# mega_connector_shield.net
KiCad netlist of a schematic drawn in EAGLE
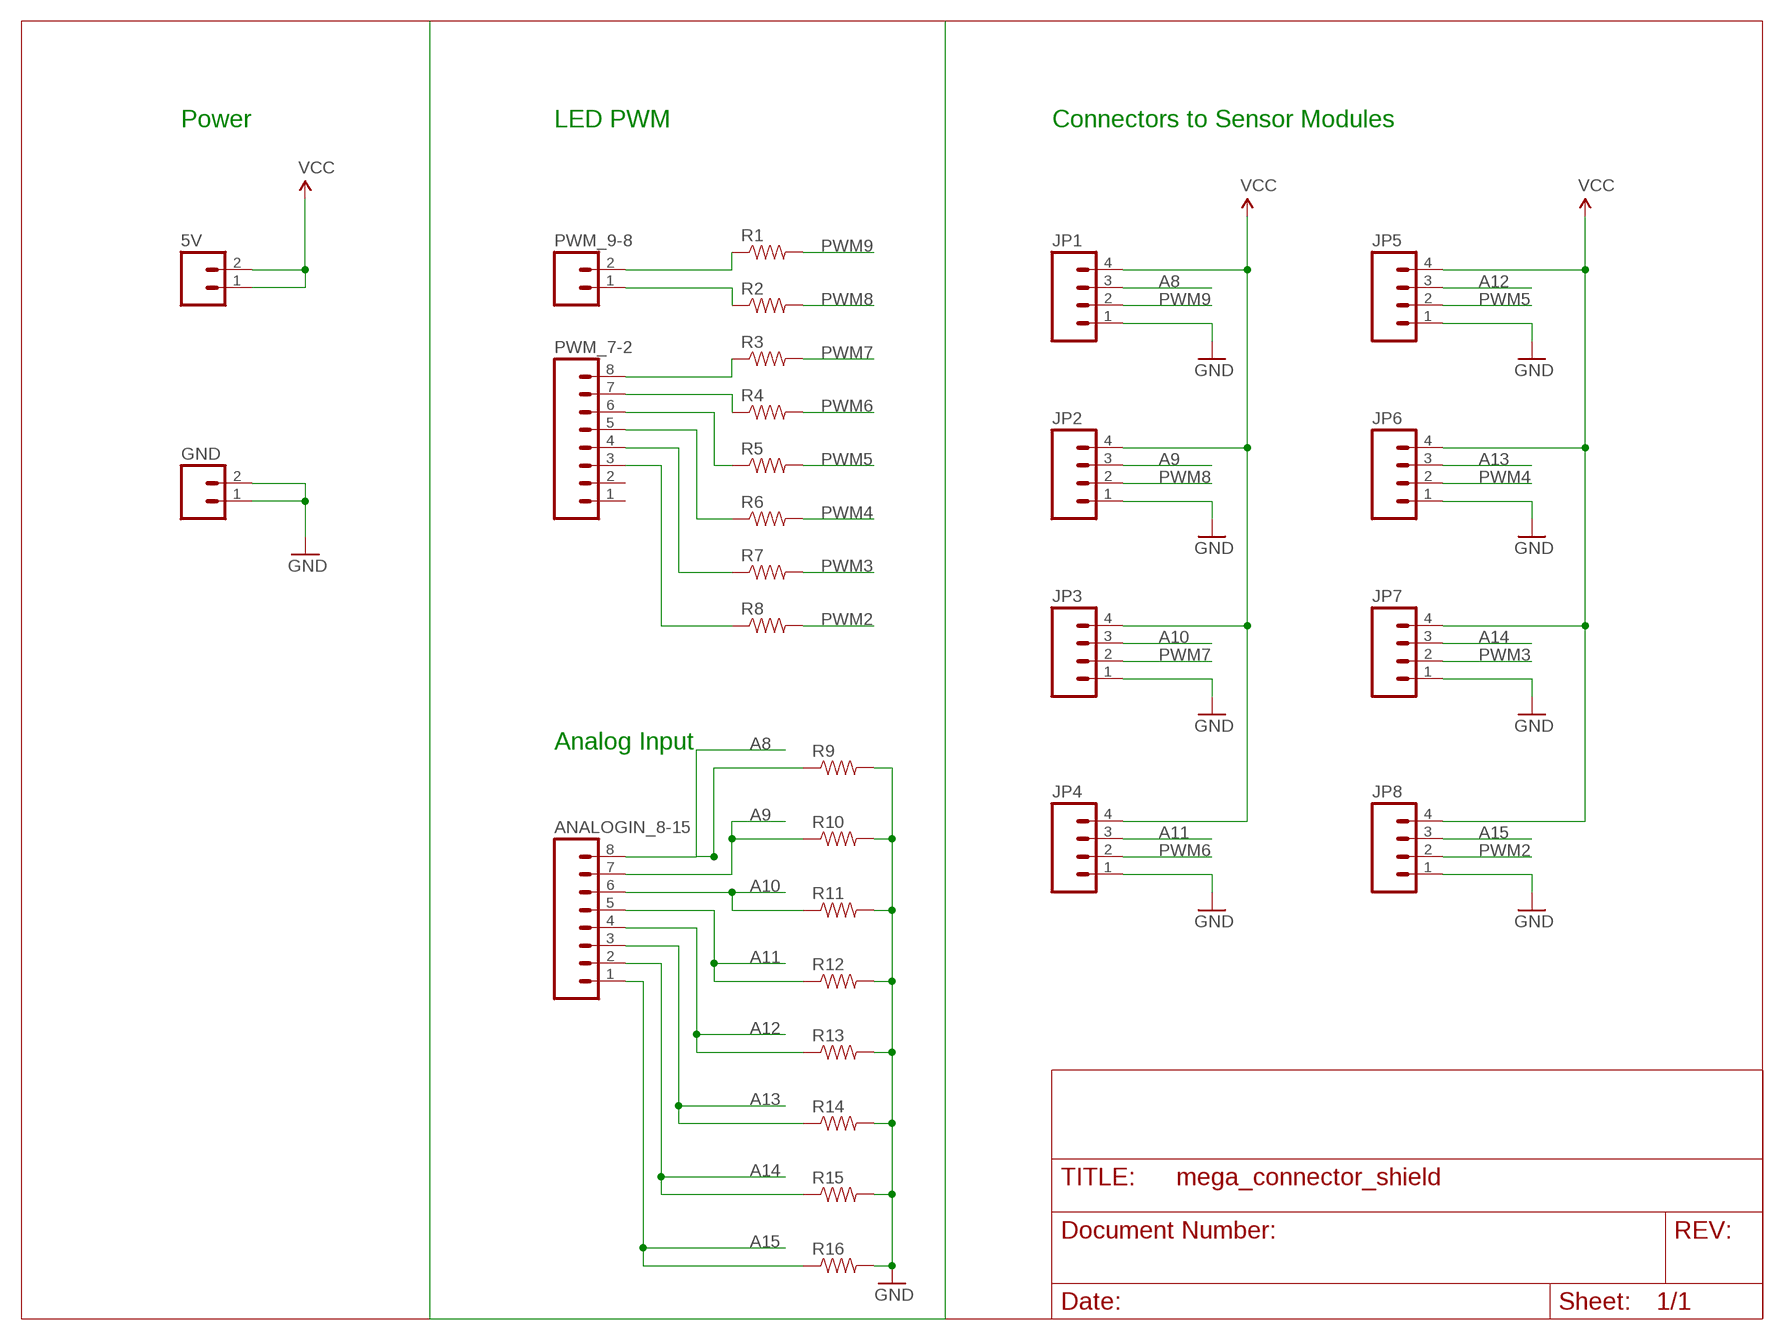
[diagram p0: schematic, sheet 1]

(export (version "E")
  (design (tool "Eeschema 10.0.6"))
  (components
    (comp (ref "5V")
      (value "M02PTH")
      (footprint "eagle-import:1X02")
      (libsource (lib "eagle-import") (part "M02PTH"))
    )
    (comp (ref "ANALOGIN_8-15")
      (value "M08")
      (footprint "eagle-import:1X08_ROUND")
      (libsource (lib "eagle-import") (part "M08"))
    )
    (comp (ref "GND")
      (value "M02PTH")
      (footprint "eagle-import:1X02")
      (libsource (lib "eagle-import") (part "M02PTH"))
    )
    (comp (ref "JP1")
      (value "M04POLAR")
      (footprint "eagle-import:MOLEX-1X4")
      (libsource (lib "eagle-import") (part "M04POLAR"))
    )
    (comp (ref "JP2")
      (value "M04POLAR")
      (footprint "eagle-import:MOLEX-1X4")
      (libsource (lib "eagle-import") (part "M04POLAR"))
    )
    (comp (ref "JP3")
      (value "M04POLAR")
      (footprint "eagle-import:MOLEX-1X4")
      (libsource (lib "eagle-import") (part "M04POLAR"))
    )
    (comp (ref "JP4")
      (value "M04POLAR")
      (footprint "eagle-import:MOLEX-1X4")
      (libsource (lib "eagle-import") (part "M04POLAR"))
    )
    (comp (ref "JP5")
      (value "M04POLAR")
      (footprint "eagle-import:MOLEX-1X4")
      (libsource (lib "eagle-import") (part "M04POLAR"))
    )
    (comp (ref "JP6")
      (value "M04POLAR")
      (footprint "eagle-import:MOLEX-1X4")
      (libsource (lib "eagle-import") (part "M04POLAR"))
    )
    (comp (ref "JP7")
      (value "M04POLAR")
      (footprint "eagle-import:MOLEX-1X4")
      (libsource (lib "eagle-import") (part "M04POLAR"))
    )
    (comp (ref "JP8")
      (value "M04POLAR")
      (footprint "eagle-import:MOLEX-1X4")
      (libsource (lib "eagle-import") (part "M04POLAR"))
    )
    (comp (ref "PWM_7-2")
      (value "M08")
      (footprint "eagle-import:1X08_ROUND")
      (libsource (lib "eagle-import") (part "M08"))
    )
    (comp (ref "PWM_9-8")
      (value "M02PTH")
      (footprint "eagle-import:1X02")
      (libsource (lib "eagle-import") (part "M02PTH"))
    )
    (comp (ref "R1")
      (value "RESISTOR1206")
      (footprint "eagle-import:1206")
      (libsource (lib "eagle-import") (part "RESISTOR1206"))
    )
    (comp (ref "R2")
      (value "RESISTOR1206")
      (footprint "eagle-import:1206")
      (libsource (lib "eagle-import") (part "RESISTOR1206"))
    )
    (comp (ref "R3")
      (value "RESISTOR1206")
      (footprint "eagle-import:1206")
      (libsource (lib "eagle-import") (part "RESISTOR1206"))
    )
    (comp (ref "R4")
      (value "RESISTOR1206")
      (footprint "eagle-import:1206")
      (libsource (lib "eagle-import") (part "RESISTOR1206"))
    )
    (comp (ref "R5")
      (value "RESISTOR1206")
      (footprint "eagle-import:1206")
      (libsource (lib "eagle-import") (part "RESISTOR1206"))
    )
    (comp (ref "R6")
      (value "RESISTOR1206")
      (footprint "eagle-import:1206")
      (libsource (lib "eagle-import") (part "RESISTOR1206"))
    )
    (comp (ref "R7")
      (value "RESISTOR1206")
      (footprint "eagle-import:1206")
      (libsource (lib "eagle-import") (part "RESISTOR1206"))
    )
    (comp (ref "R8")
      (value "RESISTOR1206")
      (footprint "eagle-import:1206")
      (libsource (lib "eagle-import") (part "RESISTOR1206"))
    )
    (comp (ref "R9")
      (value "RESISTOR1206")
      (footprint "eagle-import:1206")
      (libsource (lib "eagle-import") (part "RESISTOR1206"))
    )
    (comp (ref "R10")
      (value "RESISTOR1206")
      (footprint "eagle-import:1206")
      (libsource (lib "eagle-import") (part "RESISTOR1206"))
    )
    (comp (ref "R11")
      (value "RESISTOR1206")
      (footprint "eagle-import:1206")
      (libsource (lib "eagle-import") (part "RESISTOR1206"))
    )
    (comp (ref "R12")
      (value "RESISTOR1206")
      (footprint "eagle-import:1206")
      (libsource (lib "eagle-import") (part "RESISTOR1206"))
    )
    (comp (ref "R13")
      (value "RESISTOR1206")
      (footprint "eagle-import:1206")
      (libsource (lib "eagle-import") (part "RESISTOR1206"))
    )
    (comp (ref "R14")
      (value "RESISTOR1206")
      (footprint "eagle-import:1206")
      (libsource (lib "eagle-import") (part "RESISTOR1206"))
    )
    (comp (ref "R15")
      (value "RESISTOR1206")
      (footprint "eagle-import:1206")
      (libsource (lib "eagle-import") (part "RESISTOR1206"))
    )
    (comp (ref "R16")
      (value "RESISTOR1206")
      (footprint "eagle-import:1206")
      (libsource (lib "eagle-import") (part "RESISTOR1206"))
    )
  )
  (nets
    (net (code "1") (name "/A8") (class "Default")
      (node (ref "ANALOGIN_8-15") (pin "8") (pinfunction "8_8") (pintype "passive"))
      (node (ref "JP1") (pin "3") (pinfunction "3_3") (pintype "passive"))
      (node (ref "R9") (pin "1") (pinfunction "1_1") (pintype "passive"))
    )
    (net (code "2") (name "/A9") (class "Default")
      (node (ref "ANALOGIN_8-15") (pin "7") (pinfunction "7_7") (pintype "passive"))
      (node (ref "JP2") (pin "3") (pinfunction "3_3") (pintype "passive"))
      (node (ref "R10") (pin "1") (pinfunction "1_1") (pintype "passive"))
    )
    (net (code "3") (name "/A10") (class "Default")
      (node (ref "ANALOGIN_8-15") (pin "6") (pinfunction "6_6") (pintype "passive"))
      (node (ref "JP3") (pin "3") (pinfunction "3_3") (pintype "passive"))
      (node (ref "R11") (pin "1") (pinfunction "1_1") (pintype "passive"))
    )
    (net (code "4") (name "/A11") (class "Default")
      (node (ref "ANALOGIN_8-15") (pin "5") (pinfunction "5_5") (pintype "passive"))
      (node (ref "JP4") (pin "3") (pinfunction "3_3") (pintype "passive"))
      (node (ref "R12") (pin "1") (pinfunction "1_1") (pintype "passive"))
    )
    (net (code "5") (name "/A12") (class "Default")
      (node (ref "ANALOGIN_8-15") (pin "4") (pinfunction "4_4") (pintype "passive"))
      (node (ref "JP5") (pin "3") (pinfunction "3_3") (pintype "passive"))
      (node (ref "R13") (pin "1") (pinfunction "1_1") (pintype "passive"))
    )
    (net (code "6") (name "/A13") (class "Default")
      (node (ref "ANALOGIN_8-15") (pin "3") (pinfunction "3_3") (pintype "passive"))
      (node (ref "JP6") (pin "3") (pinfunction "3_3") (pintype "passive"))
      (node (ref "R14") (pin "1") (pinfunction "1_1") (pintype "passive"))
    )
    (net (code "7") (name "/A14") (class "Default")
      (node (ref "ANALOGIN_8-15") (pin "2") (pinfunction "2_2") (pintype "passive"))
      (node (ref "JP7") (pin "3") (pinfunction "3_3") (pintype "passive"))
      (node (ref "R15") (pin "1") (pinfunction "1_1") (pintype "passive"))
    )
    (net (code "8") (name "/A15") (class "Default")
      (node (ref "ANALOGIN_8-15") (pin "1") (pinfunction "1_1") (pintype "passive"))
      (node (ref "JP8") (pin "3") (pinfunction "3_3") (pintype "passive"))
      (node (ref "R16") (pin "1") (pinfunction "1_1") (pintype "passive"))
    )
    (net (code "9") (name "/PWM2") (class "Default")
      (node (ref "JP8") (pin "2") (pinfunction "2_2") (pintype "passive"))
      (node (ref "R8") (pin "2") (pinfunction "2_2") (pintype "passive"))
    )
    (net (code "10") (name "/PWM3") (class "Default")
      (node (ref "JP7") (pin "2") (pinfunction "2_2") (pintype "passive"))
      (node (ref "R7") (pin "2") (pinfunction "2_2") (pintype "passive"))
    )
    (net (code "11") (name "/PWM4") (class "Default")
      (node (ref "JP6") (pin "2") (pinfunction "2_2") (pintype "passive"))
      (node (ref "R6") (pin "2") (pinfunction "2_2") (pintype "passive"))
    )
    (net (code "12") (name "/PWM5") (class "Default")
      (node (ref "JP5") (pin "2") (pinfunction "2_2") (pintype "passive"))
      (node (ref "R5") (pin "2") (pinfunction "2_2") (pintype "passive"))
    )
    (net (code "13") (name "/PWM6") (class "Default")
      (node (ref "JP4") (pin "2") (pinfunction "2_2") (pintype "passive"))
      (node (ref "R4") (pin "2") (pinfunction "2_2") (pintype "passive"))
    )
    (net (code "14") (name "/PWM7") (class "Default")
      (node (ref "JP3") (pin "2") (pinfunction "2_2") (pintype "passive"))
      (node (ref "R3") (pin "2") (pinfunction "2_2") (pintype "passive"))
    )
    (net (code "15") (name "/PWM8") (class "Default")
      (node (ref "JP2") (pin "2") (pinfunction "2_2") (pintype "passive"))
      (node (ref "R2") (pin "2") (pinfunction "2_2") (pintype "passive"))
    )
    (net (code "16") (name "/PWM9") (class "Default")
      (node (ref "JP1") (pin "2") (pinfunction "2_2") (pintype "passive"))
      (node (ref "R1") (pin "2") (pinfunction "2_2") (pintype "passive"))
    )
    (net (code "17") (name "GND") (class "Default")
      (node (ref "GND") (pin "1") (pinfunction "1_1") (pintype "passive"))
      (node (ref "GND") (pin "2") (pinfunction "2_2") (pintype "passive"))
      (node (ref "JP1") (pin "1") (pinfunction "1_1") (pintype "passive"))
      (node (ref "JP2") (pin "1") (pinfunction "1_1") (pintype "passive"))
      (node (ref "JP3") (pin "1") (pinfunction "1_1") (pintype "passive"))
      (node (ref "JP4") (pin "1") (pinfunction "1_1") (pintype "passive"))
      (node (ref "JP5") (pin "1") (pinfunction "1_1") (pintype "passive"))
      (node (ref "JP6") (pin "1") (pinfunction "1_1") (pintype "passive"))
      (node (ref "JP7") (pin "1") (pinfunction "1_1") (pintype "passive"))
      (node (ref "JP8") (pin "1") (pinfunction "1_1") (pintype "passive"))
      (node (ref "R10") (pin "2") (pinfunction "2_2") (pintype "passive"))
      (node (ref "R11") (pin "2") (pinfunction "2_2") (pintype "passive"))
      (node (ref "R12") (pin "2") (pinfunction "2_2") (pintype "passive"))
      (node (ref "R13") (pin "2") (pinfunction "2_2") (pintype "passive"))
      (node (ref "R14") (pin "2") (pinfunction "2_2") (pintype "passive"))
      (node (ref "R15") (pin "2") (pinfunction "2_2") (pintype "passive"))
      (node (ref "R16") (pin "2") (pinfunction "2_2") (pintype "passive"))
      (node (ref "R9") (pin "2") (pinfunction "2_2") (pintype "passive"))
    )
    (net (code "18") (name "Net-(PWM_7-2-Pad3)") (class "Default")
      (node (ref "PWM_7-2") (pin "3") (pinfunction "3_3") (pintype "passive"))
      (node (ref "R8") (pin "1") (pinfunction "1_1") (pintype "passive"))
    )
    (net (code "19") (name "Net-(PWM_7-2-Pad4)") (class "Default")
      (node (ref "PWM_7-2") (pin "4") (pinfunction "4_4") (pintype "passive"))
      (node (ref "R7") (pin "1") (pinfunction "1_1") (pintype "passive"))
    )
    (net (code "20") (name "Net-(PWM_7-2-Pad5)") (class "Default")
      (node (ref "PWM_7-2") (pin "5") (pinfunction "5_5") (pintype "passive"))
      (node (ref "R6") (pin "1") (pinfunction "1_1") (pintype "passive"))
    )
    (net (code "21") (name "Net-(PWM_7-2-Pad6)") (class "Default")
      (node (ref "PWM_7-2") (pin "6") (pinfunction "6_6") (pintype "passive"))
      (node (ref "R5") (pin "1") (pinfunction "1_1") (pintype "passive"))
    )
    (net (code "22") (name "Net-(PWM_7-2-Pad7)") (class "Default")
      (node (ref "PWM_7-2") (pin "7") (pinfunction "7_7") (pintype "passive"))
      (node (ref "R4") (pin "1") (pinfunction "1_1") (pintype "passive"))
    )
    (net (code "23") (name "Net-(PWM_7-2-Pad8)") (class "Default")
      (node (ref "PWM_7-2") (pin "8") (pinfunction "8_8") (pintype "passive"))
      (node (ref "R3") (pin "1") (pinfunction "1_1") (pintype "passive"))
    )
    (net (code "24") (name "Net-(PWM_9-8-Pad1)") (class "Default")
      (node (ref "PWM_9-8") (pin "1") (pinfunction "1_1") (pintype "passive"))
      (node (ref "R2") (pin "1") (pinfunction "1_1") (pintype "passive"))
    )
    (net (code "25") (name "Net-(PWM_9-8-Pad2)") (class "Default")
      (node (ref "PWM_9-8") (pin "2") (pinfunction "2_2") (pintype "passive"))
      (node (ref "R1") (pin "1") (pinfunction "1_1") (pintype "passive"))
    )
    (net (code "26") (name "VCC") (class "Default")
      (node (ref "5V") (pin "1") (pinfunction "1_1") (pintype "passive"))
      (node (ref "5V") (pin "2") (pinfunction "2_2") (pintype "passive"))
      (node (ref "JP1") (pin "4") (pinfunction "4_4") (pintype "passive"))
      (node (ref "JP2") (pin "4") (pinfunction "4_4") (pintype "passive"))
      (node (ref "JP3") (pin "4") (pinfunction "4_4") (pintype "passive"))
      (node (ref "JP4") (pin "4") (pinfunction "4_4") (pintype "passive"))
      (node (ref "JP5") (pin "4") (pinfunction "4_4") (pintype "passive"))
      (node (ref "JP6") (pin "4") (pinfunction "4_4") (pintype "passive"))
      (node (ref "JP7") (pin "4") (pinfunction "4_4") (pintype "passive"))
      (node (ref "JP8") (pin "4") (pinfunction "4_4") (pintype "passive"))
    )
    (net (code "27") (name "unconnected-(PWM_7-2-Pad1)") (class "Default")
      (node (ref "PWM_7-2") (pin "1") (pinfunction "1_1") (pintype "passive"))
    )
    (net (code "28") (name "unconnected-(PWM_7-2-Pad2)") (class "Default")
      (node (ref "PWM_7-2") (pin "2") (pinfunction "2_2") (pintype "passive"))
    )
  )
)
